# M_N_ext_connector.net
KiCad netlist of a schematic drawn in EAGLE
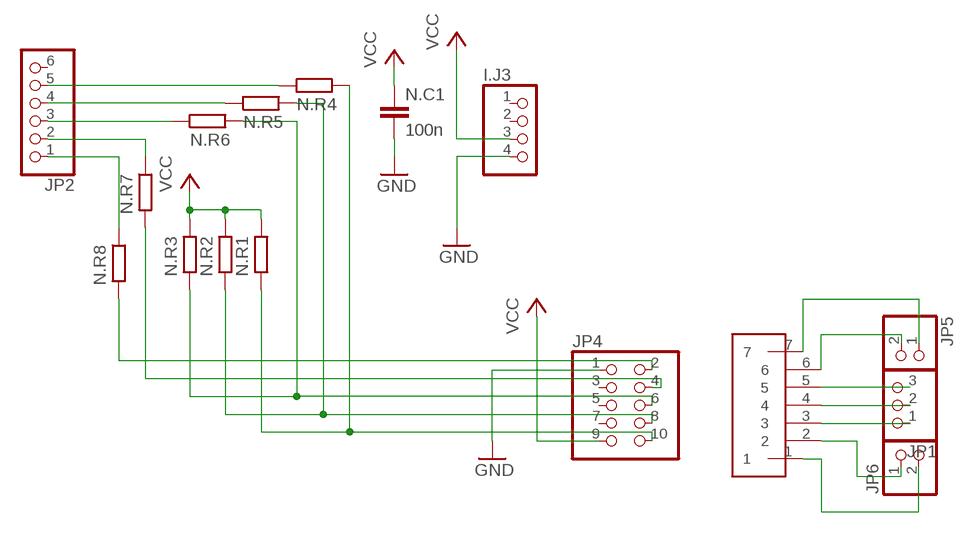
[diagram p0: schematic, sheet 1]

(export (version "E")
  (design (tool "Eeschema 10.0.6"))
  (components
    (comp (ref "I.J3")
      (value "PINHD-1X4")
      (footprint "eagle-import:1X04")
      (libsource (lib "eagle-import") (part "PINHD-1X4"))
    )
    (comp (ref "JP1")
      (value "PINHD-1X3")
      (footprint "eagle-import:1X03")
      (libsource (lib "eagle-import") (part "PINHD-1X3"))
    )
    (comp (ref "JP2")
      (value "PINHD-1X6")
      (footprint "eagle-import:1X06")
      (libsource (lib "eagle-import") (part "PINHD-1X6"))
    )
    (comp (ref "JP4")
      (value "PINHD-2X5/90")
      (footprint "eagle-import:2X05_90")
      (libsource (lib "eagle-import") (part "PINHD-2X5/90"))
    )
    (comp (ref "JP5")
      (value "PINHD-1X2")
      (footprint "eagle-import:1X02")
      (libsource (lib "eagle-import") (part "PINHD-1X2"))
    )
    (comp (ref "JP6")
      (value "PINHD-1X2")
      (footprint "eagle-import:1X02")
      (libsource (lib "eagle-import") (part "PINHD-1X2"))
    )
    (comp (ref "N.C1")
      (value "100n")
      (footprint "eagle-import:C0603")
      (libsource (lib "eagle-import") (part "C-EUC0603"))
    )
    (comp (ref "N.R1")
      (value "4k7")
      (footprint "eagle-import:R0603")
      (libsource (lib "eagle-import") (part "R-EU_R0603"))
    )
    (comp (ref "N.R2")
      (value "4k7")
      (footprint "eagle-import:R0603")
      (libsource (lib "eagle-import") (part "R-EU_R0603"))
    )
    (comp (ref "N.R3")
      (value "4k7")
      (footprint "eagle-import:R0603")
      (libsource (lib "eagle-import") (part "R-EU_R0603"))
    )
    (comp (ref "N.R4")
      (value "4k7")
      (footprint "eagle-import:R0603")
      (libsource (lib "eagle-import") (part "R-EU_R0603"))
    )
    (comp (ref "N.R5")
      (value "4k7")
      (footprint "eagle-import:R0603")
      (libsource (lib "eagle-import") (part "R-EU_R0603"))
    )
    (comp (ref "N.R6")
      (value "4k7")
      (footprint "eagle-import:R0603")
      (libsource (lib "eagle-import") (part "R-EU_R0603"))
    )
    (comp (ref "N.R7")
      (value "4k7")
      (footprint "eagle-import:R0603")
      (libsource (lib "eagle-import") (part "R-EU_R0603"))
    )
    (comp (ref "N.R8")
      (value "4k7")
      (footprint "eagle-import:R0603")
      (libsource (lib "eagle-import") (part "R-EU_R0603"))
    )
    (comp (ref "U$1")
      (value "7PIN_CONNECTOR")
      (footprint "eagle-import:7PIN_CONNECTOR")
      (libsource (lib "eagle-import") (part "7PIN_CONNECTOR"))
    )
  )
  (nets
    (net (code "1") (name "GND") (class "Default")
      (node (ref "I.J3") (pin "4") (pinfunction "4_4") (pintype "passive"))
      (node (ref "JP4") (pin "1") (pinfunction "1_1") (pintype "passive"))
      (node (ref "N.C1") (pin "2") (pinfunction "2_2") (pintype "passive"))
    )
    (net (code "2") (name "Net-(JP1-Pad1)") (class "Default")
      (node (ref "JP1") (pin "1") (pinfunction "1_1") (pintype "passive"))
      (node (ref "U$1") (pin "3") (pinfunction "3_3") (pintype "bidirectional"))
    )
    (net (code "3") (name "Net-(JP1-Pad2)") (class "Default")
      (node (ref "JP1") (pin "2") (pinfunction "2_2") (pintype "passive"))
      (node (ref "U$1") (pin "4") (pinfunction "4_4") (pintype "bidirectional"))
    )
    (net (code "4") (name "Net-(JP1-Pad3)") (class "Default")
      (node (ref "JP1") (pin "3") (pinfunction "3_3") (pintype "passive"))
      (node (ref "U$1") (pin "5") (pinfunction "5_5") (pintype "bidirectional"))
    )
    (net (code "5") (name "Net-(JP2-Pad1)") (class "Default")
      (node (ref "JP2") (pin "1") (pinfunction "1_1") (pintype "passive"))
      (node (ref "N.R8") (pin "1") (pinfunction "1_1") (pintype "passive"))
    )
    (net (code "6") (name "Net-(JP2-Pad2)") (class "Default")
      (node (ref "JP2") (pin "2") (pinfunction "2_2") (pintype "passive"))
      (node (ref "N.R7") (pin "1") (pinfunction "1_1") (pintype "passive"))
    )
    (net (code "7") (name "Net-(JP2-Pad3)") (class "Default")
      (node (ref "JP2") (pin "3") (pinfunction "3_3") (pintype "passive"))
      (node (ref "N.R6") (pin "1") (pinfunction "1_1") (pintype "passive"))
    )
    (net (code "8") (name "Net-(JP2-Pad4)") (class "Default")
      (node (ref "JP2") (pin "4") (pinfunction "4_4") (pintype "passive"))
      (node (ref "N.R5") (pin "1") (pinfunction "1_1") (pintype "passive"))
    )
    (net (code "9") (name "Net-(JP2-Pad5)") (class "Default")
      (node (ref "JP2") (pin "5") (pinfunction "5_5") (pintype "passive"))
      (node (ref "N.R4") (pin "1") (pinfunction "1_1") (pintype "passive"))
    )
    (net (code "10") (name "Net-(JP4-Pad2)") (class "Default")
      (node (ref "JP4") (pin "2") (pinfunction "2_2") (pintype "passive"))
      (node (ref "N.R8") (pin "2") (pinfunction "2_2") (pintype "passive"))
    )
    (net (code "11") (name "Net-(JP4-Pad4)") (class "Default")
      (node (ref "JP4") (pin "4") (pinfunction "4_4") (pintype "passive"))
      (node (ref "N.R7") (pin "2") (pinfunction "2_2") (pintype "passive"))
    )
    (net (code "12") (name "Net-(JP4-Pad6)") (class "Default")
      (node (ref "JP4") (pin "6") (pinfunction "6_6") (pintype "passive"))
      (node (ref "N.R3") (pin "2") (pinfunction "2_2") (pintype "passive"))
      (node (ref "N.R6") (pin "2") (pinfunction "2_2") (pintype "passive"))
    )
    (net (code "13") (name "Net-(JP4-Pad8)") (class "Default")
      (node (ref "JP4") (pin "8") (pinfunction "8_8") (pintype "passive"))
      (node (ref "N.R2") (pin "2") (pinfunction "2_2") (pintype "passive"))
      (node (ref "N.R5") (pin "2") (pinfunction "2_2") (pintype "passive"))
    )
    (net (code "14") (name "Net-(JP4-Pad10)") (class "Default")
      (node (ref "JP4") (pin "10") (pinfunction "10_10") (pintype "passive"))
      (node (ref "N.R1") (pin "2") (pinfunction "2_2") (pintype "passive"))
      (node (ref "N.R4") (pin "2") (pinfunction "2_2") (pintype "passive"))
    )
    (net (code "15") (name "Net-(JP5-Pad1)") (class "Default")
      (node (ref "JP5") (pin "1") (pinfunction "1_1") (pintype "passive"))
      (node (ref "U$1") (pin "7") (pinfunction "7_7") (pintype "bidirectional"))
    )
    (net (code "16") (name "Net-(JP5-Pad2)") (class "Default")
      (node (ref "JP5") (pin "2") (pinfunction "2_2") (pintype "passive"))
      (node (ref "U$1") (pin "6") (pinfunction "6_6") (pintype "bidirectional"))
    )
    (net (code "17") (name "Net-(JP6-Pad1)") (class "Default")
      (node (ref "JP6") (pin "1") (pinfunction "1_1") (pintype "passive"))
      (node (ref "U$1") (pin "2") (pinfunction "2_2") (pintype "bidirectional"))
    )
    (net (code "18") (name "Net-(JP6-Pad2)") (class "Default")
      (node (ref "JP6") (pin "2") (pinfunction "2_2") (pintype "passive"))
      (node (ref "U$1") (pin "1") (pinfunction "1_1") (pintype "bidirectional"))
    )
    (net (code "19") (name "VCC") (class "Default")
      (node (ref "I.J3") (pin "3") (pinfunction "3_3") (pintype "passive"))
      (node (ref "JP4") (pin "9") (pinfunction "9_9") (pintype "passive"))
      (node (ref "N.C1") (pin "1") (pinfunction "1_1") (pintype "passive"))
      (node (ref "N.R1") (pin "1") (pinfunction "1_1") (pintype "passive"))
      (node (ref "N.R2") (pin "1") (pinfunction "1_1") (pintype "passive"))
      (node (ref "N.R3") (pin "1") (pinfunction "1_1") (pintype "passive"))
    )
    (net (code "20") (name "unconnected-(I.J3-Pad1)") (class "Default")
      (node (ref "I.J3") (pin "1") (pinfunction "1_1") (pintype "passive"))
    )
    (net (code "21") (name "unconnected-(I.J3-Pad2)") (class "Default")
      (node (ref "I.J3") (pin "2") (pinfunction "2_2") (pintype "passive"))
    )
    (net (code "22") (name "unconnected-(JP2-Pad6)") (class "Default")
      (node (ref "JP2") (pin "6") (pinfunction "6_6") (pintype "passive"))
    )
    (net (code "23") (name "unconnected-(JP4-Pad3)") (class "Default")
      (node (ref "JP4") (pin "3") (pinfunction "3_3") (pintype "passive"))
    )
    (net (code "24") (name "unconnected-(JP4-Pad5)") (class "Default")
      (node (ref "JP4") (pin "5") (pinfunction "5_5") (pintype "passive"))
    )
    (net (code "25") (name "unconnected-(JP4-Pad7)") (class "Default")
      (node (ref "JP4") (pin "7") (pinfunction "7_7") (pintype "passive"))
    )
  )
)
